# OTAVCF.net
KiCad netlist of a schematic drawn in EAGLE
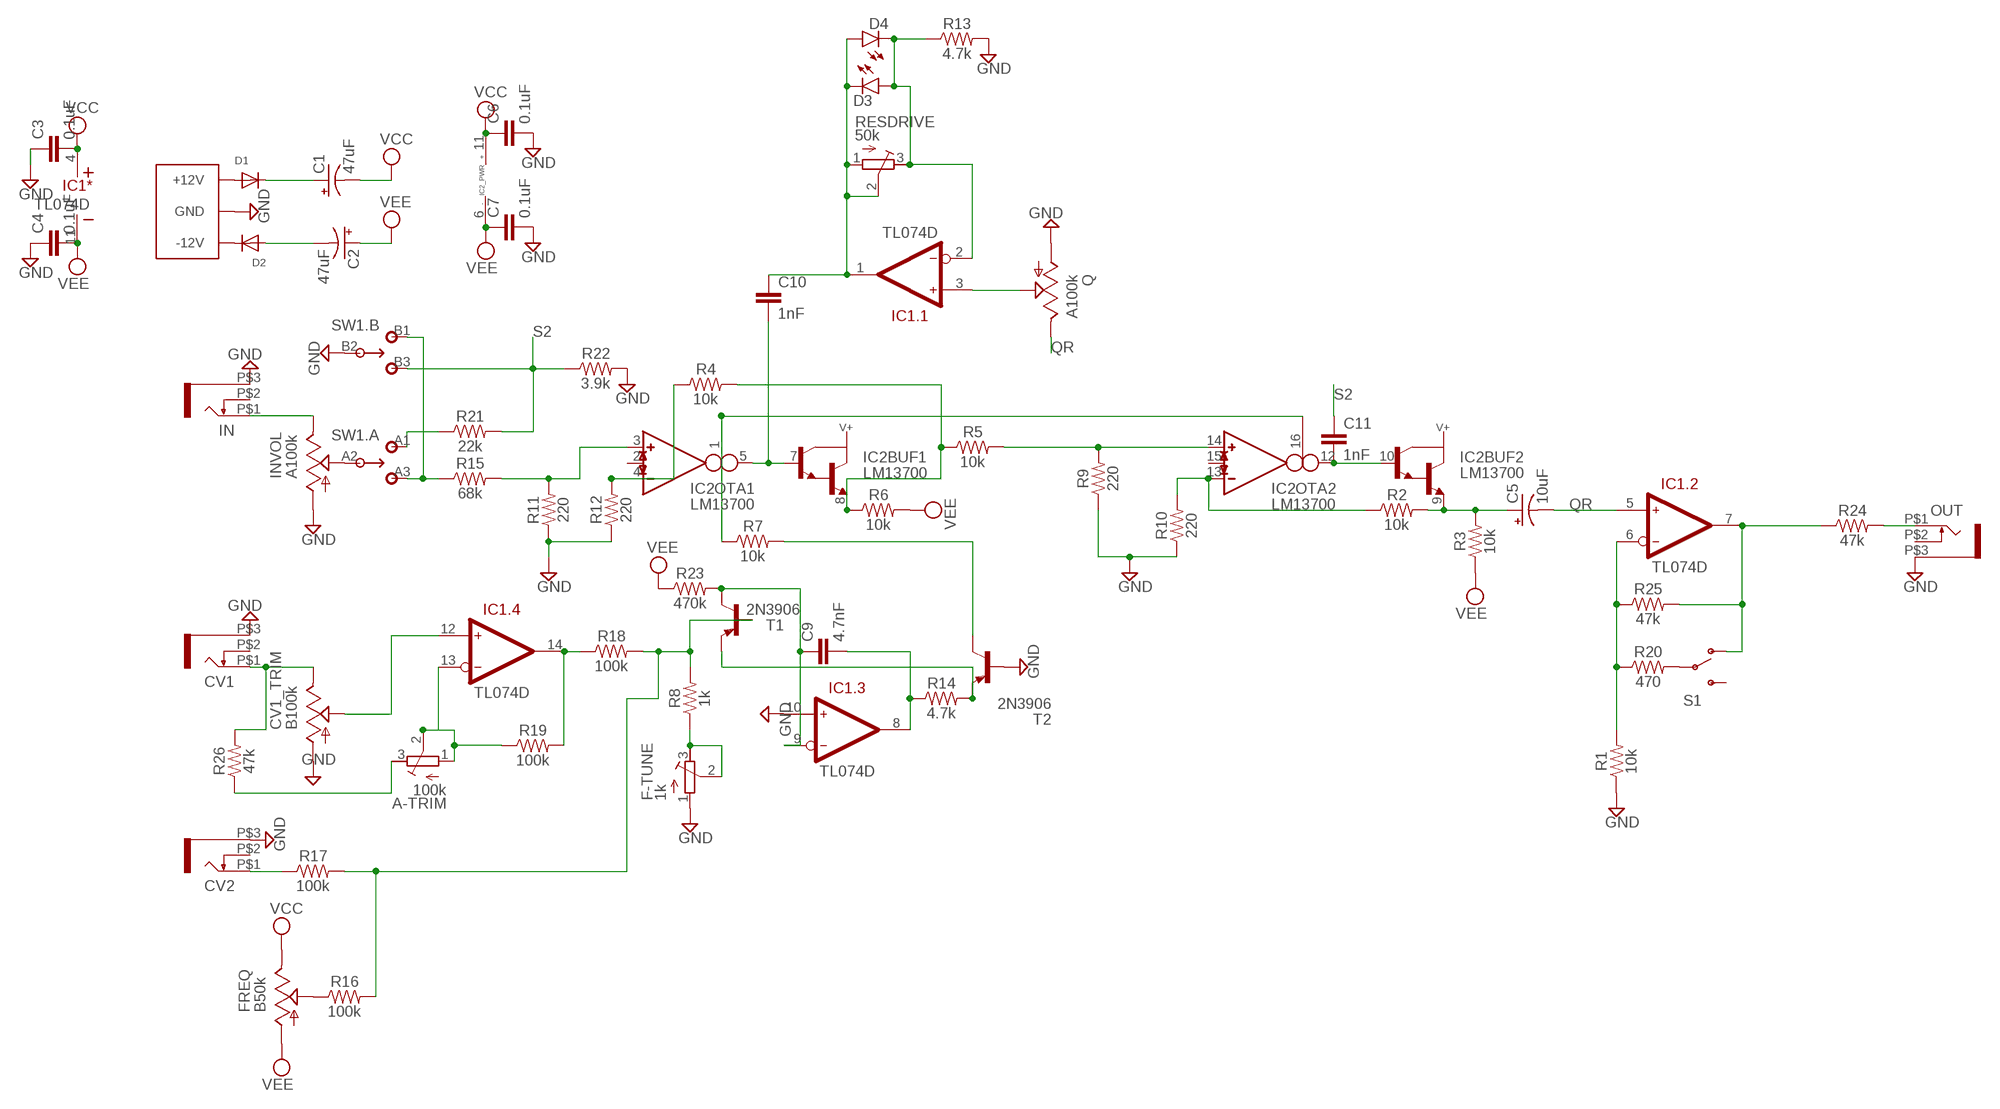
[diagram p0: schematic, sheet 1]

(export (version "E")
  (design (tool "Eeschema 10.0.6"))
  (components
    (comp (ref "A-TRIM")
      (value "100k")
      (footprint "eagle-import:RTRIM3296W")
      (libsource (lib "eagle-import") (part "R-TRIMM3296W"))
    )
    (comp (ref "C1")
      (value "47uF")
      (footprint "eagle-import:PAN_B_SMD+THRU")
      (libsource (lib "eagle-import") (part "CAP_SMD+THRUPAN_B"))
    )
    (comp (ref "C2")
      (value "47uF")
      (footprint "eagle-import:PAN_B_SMD+THRU")
      (libsource (lib "eagle-import") (part "CAP_SMD+THRUPAN_B"))
    )
    (comp (ref "C3")
      (value "0.1uF")
      (footprint "eagle-import:0603")
      (libsource (lib "eagle-import") (part "0.1UF-0603-25V-(+80/-20%)"))
    )
    (comp (ref "C4")
      (value "0.1uF")
      (footprint "eagle-import:0603")
      (libsource (lib "eagle-import") (part "0.1UF-0603-25V-(+80/-20%)"))
    )
    (comp (ref "C5")
      (value "10uF")
      (footprint "eagle-import:CPOL-RADIAL-2.5MM-5MM")
      (libsource (lib "eagle-import") (part "10UF-POLAR-RADIAL-2.5MM-25V-20%"))
    )
    (comp (ref "C6")
      (value "0.1uF")
      (footprint "eagle-import:0603")
      (libsource (lib "eagle-import") (part "0.1UF-0603-25V-(+80/-20%)"))
    )
    (comp (ref "C7")
      (value "0.1uF")
      (footprint "eagle-import:0603")
      (libsource (lib "eagle-import") (part "0.1UF-0603-25V-(+80/-20%)"))
    )
    (comp (ref "C9")
      (value "4.7nF")
      (footprint "eagle-import:0603")
      (libsource (lib "eagle-import") (part "0.1UF-0603-25V-(+80/-20%)"))
    )
    (comp (ref "C10")
      (value "1nF")
      (footprint "eagle-import:0603")
      (libsource (lib "eagle-import") (part "1.0NF/1000PF-0603-50V-10%"))
    )
    (comp (ref "C11")
      (value "1nF")
      (footprint "eagle-import:0603")
      (libsource (lib "eagle-import") (part "1.0NF/1000PF-0603-50V-10%"))
    )
    (comp (ref "CV1")
      (value "WQP-PJ301M-12_JACK")
      (footprint "eagle-import:WQP-PJ301M-12_JACK")
      (libsource (lib "eagle-import") (part "WQP-PJ301M-12_JACK"))
    )
    (comp (ref "CV1_TRIM")
      (value "B100k")
      (footprint "eagle-import:9MM_SNAP-IN_POT")
      (libsource (lib "eagle-import") (part "9MM_SNAP-IN_POT_"))
    )
    (comp (ref "CV2")
      (value "WQP-PJ301M-12_JACK")
      (footprint "eagle-import:WQP-PJ301M-12_JACK")
      (libsource (lib "eagle-import") (part "WQP-PJ301M-12_JACK"))
    )
    (comp (ref "D1")
      (value "DIODESOD-123")
      (footprint "eagle-import:SOD-123")
      (libsource (lib "eagle-import") (part "DIODESOD-123"))
    )
    (comp (ref "D2")
      (value "DIODESOD-123")
      (footprint "eagle-import:SOD-123")
      (libsource (lib "eagle-import") (part "DIODESOD-123"))
    )
    (comp (ref "D3")
      (value "LED.3")
      (footprint "eagle-import:3MM_2")
      (libsource (lib "eagle-import") (part "LED.3"))
    )
    (comp (ref "D4")
      (value "LED.3")
      (footprint "eagle-import:3MM_2")
      (libsource (lib "eagle-import") (part "LED.3"))
    )
    (comp (ref "F-TUNE")
      (value "1k")
      (footprint "eagle-import:RTRIM3296W")
      (libsource (lib "eagle-import") (part "R-TRIMM3296W"))
    )
    (comp (ref "FREQ")
      (value "B50k")
      (footprint "eagle-import:9MM_SNAP-IN_POT")
      (libsource (lib "eagle-import") (part "9MM_SNAP-IN_POT_"))
    )
    (comp (ref "IC1")
      (value "TL074D")
      (footprint "eagle-import:SO-14")
      (libsource (lib "eagle-import") (part "TL074D"))
    )
    (comp (ref "IC2")
      (value "LM13700")
      (footprint "eagle-import:SO16")
      (libsource (lib "eagle-import") (part "LM13X00_SMT"))
    )
    (comp (ref "IN")
      (value "WQP-PJ301M-12_JACK")
      (footprint "eagle-import:WQP-PJ301M-12_JACK")
      (libsource (lib "eagle-import") (part "WQP-PJ301M-12_JACK"))
    )
    (comp (ref "INVOL")
      (value "A100k")
      (footprint "eagle-import:9MM_SNAP-IN_POT")
      (libsource (lib "eagle-import") (part "9MM_SNAP-IN_POT_"))
    )
    (comp (ref "OUT")
      (value "WQP-PJ301M-12_JACK")
      (footprint "eagle-import:WQP-PJ301M-12_JACK")
      (libsource (lib "eagle-import") (part "WQP-PJ301M-12_JACK"))
    )
    (comp (ref "Q")
      (value "A100k")
      (footprint "eagle-import:9MM_SNAP-IN_POT")
      (libsource (lib "eagle-import") (part "9MM_SNAP-IN_POT_"))
    )
    (comp (ref "R1")
      (value "10k")
      (footprint "eagle-import:0603")
      (libsource (lib "eagle-import") (part "10KOHM-0603-1/10W-1%"))
    )
    (comp (ref "R2")
      (value "10k")
      (footprint "eagle-import:0603")
      (libsource (lib "eagle-import") (part "10KOHM-0603-1/10W-1%"))
    )
    (comp (ref "R3")
      (value "10k")
      (footprint "eagle-import:0603")
      (libsource (lib "eagle-import") (part "10KOHM-0603-1/10W-1%"))
    )
    (comp (ref "R4")
      (value "10k")
      (footprint "eagle-import:0603")
      (libsource (lib "eagle-import") (part "10KOHM-0603-1/10W-1%"))
    )
    (comp (ref "R5")
      (value "10k")
      (footprint "eagle-import:0603")
      (libsource (lib "eagle-import") (part "10KOHM-0603-1/10W-1%"))
    )
    (comp (ref "R6")
      (value "10k")
      (footprint "eagle-import:0603")
      (libsource (lib "eagle-import") (part "10KOHM-0603-1/10W-1%"))
    )
    (comp (ref "R7")
      (value "10k")
      (footprint "eagle-import:0603")
      (libsource (lib "eagle-import") (part "10KOHM-0603-1/10W-1%"))
    )
    (comp (ref "R8")
      (value "1k")
      (footprint "eagle-import:0603")
      (libsource (lib "eagle-import") (part "1KOHM-0603-1/10W-1%"))
    )
    (comp (ref "R9")
      (value "220")
      (footprint "eagle-import:0603")
      (libsource (lib "eagle-import") (part "220OHM-0603-1/10W-1%"))
    )
    (comp (ref "R10")
      (value "220")
      (footprint "eagle-import:0603")
      (libsource (lib "eagle-import") (part "220OHM-0603-1/10W-1%"))
    )
    (comp (ref "R11")
      (value "220")
      (footprint "eagle-import:0603")
      (libsource (lib "eagle-import") (part "220OHM-0603-1/10W-1%"))
    )
    (comp (ref "R12")
      (value "220")
      (footprint "eagle-import:0603")
      (libsource (lib "eagle-import") (part "220OHM-0603-1/10W-1%"))
    )
    (comp (ref "R13")
      (value "4.7k")
      (footprint "eagle-import:0603")
      (libsource (lib "eagle-import") (part "4.7KOHM-0603-1/10W-1%"))
    )
    (comp (ref "R14")
      (value "4.7k")
      (footprint "eagle-import:0603")
      (libsource (lib "eagle-import") (part "4.7KOHM-0603-1/10W-1%"))
    )
    (comp (ref "R15")
      (value "68k")
      (footprint "eagle-import:0603")
      (libsource (lib "eagle-import") (part "RESISTOR0603"))
    )
    (comp (ref "R16")
      (value "100k")
      (footprint "eagle-import:0603")
      (libsource (lib "eagle-import") (part "100KOHM-0603-1/10W-1%"))
    )
    (comp (ref "R17")
      (value "100k")
      (footprint "eagle-import:0603")
      (libsource (lib "eagle-import") (part "100KOHM-0603-1/10W-1%"))
    )
    (comp (ref "R18")
      (value "100k")
      (footprint "eagle-import:0603")
      (libsource (lib "eagle-import") (part "100KOHM-0603-1/10W-1%"))
    )
    (comp (ref "R19")
      (value "100k")
      (footprint "eagle-import:0603")
      (libsource (lib "eagle-import") (part "100KOHM-0603-1/10W-1%"))
    )
    (comp (ref "R20")
      (value "470")
      (footprint "eagle-import:0603")
      (libsource (lib "eagle-import") (part "470OHM-0603-1/10W-1%"))
    )
    (comp (ref "R21")
      (value "22k")
      (footprint "eagle-import:0603")
      (libsource (lib "eagle-import") (part "22KOHM-0603-1/10W-1%"))
    )
    (comp (ref "R22")
      (value "3.9k")
      (footprint "eagle-import:0603")
      (libsource (lib "eagle-import") (part "3.9KOHM-0603-1/10W-1%"))
    )
    (comp (ref "R23")
      (value "470k")
      (footprint "eagle-import:0603")
      (libsource (lib "eagle-import") (part "RESISTOR0603"))
    )
    (comp (ref "R24")
      (value "47k")
      (footprint "eagle-import:0603")
      (libsource (lib "eagle-import") (part "47KOHM-0603-1/10W-1%"))
    )
    (comp (ref "R25")
      (value "47k")
      (footprint "eagle-import:0603")
      (libsource (lib "eagle-import") (part "47KOHM-0603-1/10W-1%"))
    )
    (comp (ref "R26")
      (value "47k")
      (footprint "eagle-import:0603")
      (libsource (lib "eagle-import") (part "47KOHM-0603-1/10W-1%"))
    )
    (comp (ref "RESDRIVE")
      (value "50k")
      (footprint "eagle-import:RTRIM3296W")
      (libsource (lib "eagle-import") (part "R-TRIMM3296W"))
    )
    (comp (ref "S1")
      (value "SUBMINI_SPDT")
      (footprint "eagle-import:SUBMINI_TOGGLE")
      (libsource (lib "eagle-import") (part "SUBMINI_SPDT"))
    )
    (comp (ref "SW1")
      (value "DPDT.LUGS")
      (footprint "eagle-import:DPDT.LUGS")
      (libsource (lib "eagle-import") (part "DPDT.LUGS"))
    )
    (comp (ref "T1")
      (value "2N3906")
      (footprint "eagle-import:SOT23-BEC")
      (libsource (lib "eagle-import") (part "-PNP-SOT23-BECBC807-40"))
    )
    (comp (ref "T2")
      (value "2N3906")
      (footprint "eagle-import:SOT23-BEC")
      (libsource (lib "eagle-import") (part "-PNP-SOT23-BECBC807-40"))
    )
    (comp (ref "U$1")
      (value "EURO_POWER_LOCK")
      (footprint "eagle-import:EURO_PWR_HEADER_LOCK")
      (libsource (lib "eagle-import") (part "EURO_POWER_LOCK"))
    )
  )
  (nets
    (net (code "1") (name "/QR") (class "Default")
      (node (ref "C5") (pin "2") (pinfunction "-_2") (pintype "passive"))
      (node (ref "IC1") (pin "5") (pinfunction "IN+_5") (pintype "input"))
      (node (ref "Q") (pin "3") (pinfunction "E_3") (pintype "passive"))
    )
    (net (code "2") (name "/S2") (class "Default")
      (node (ref "C11") (pin "1") (pinfunction "1_1") (pintype "passive"))
      (node (ref "R21") (pin "2") (pinfunction "2_2") (pintype "passive"))
      (node (ref "R22") (pin "1") (pinfunction "1_1") (pintype "passive"))
      (node (ref "SW1") (pin "B3") (pinfunction "3_B3") (pintype "passive"))
    )
    (net (code "3") (name "GND") (class "Default")
      (node (ref "C3") (pin "1") (pinfunction "1_1") (pintype "passive"))
      (node (ref "C4") (pin "1") (pinfunction "1_1") (pintype "passive"))
      (node (ref "C6") (pin "2") (pinfunction "2_2") (pintype "passive"))
      (node (ref "C7") (pin "2") (pinfunction "2_2") (pintype "passive"))
      (node (ref "CV1") (pin "P$3") (pinfunction "1_P$3") (pintype "passive"))
      (node (ref "CV1_TRIM") (pin "1") (pinfunction "A_1") (pintype "passive"))
      (node (ref "CV2") (pin "P$3") (pinfunction "1_P$3") (pintype "passive"))
      (node (ref "F-TUNE") (pin "1") (pinfunction "A_1") (pintype "passive"))
      (node (ref "IC1") (pin "10") (pinfunction "IN+_10") (pintype "input"))
      (node (ref "IN") (pin "P$3") (pinfunction "1_P$3") (pintype "passive"))
      (node (ref "INVOL") (pin "1") (pinfunction "A_1") (pintype "passive"))
      (node (ref "OUT") (pin "P$3") (pinfunction "1_P$3") (pintype "passive"))
      (node (ref "Q") (pin "1") (pinfunction "A_1") (pintype "passive"))
      (node (ref "R1") (pin "1") (pinfunction "1_1") (pintype "passive"))
      (node (ref "R10") (pin "1") (pinfunction "1_1") (pintype "passive"))
      (node (ref "R11") (pin "1") (pinfunction "1_1") (pintype "passive"))
      (node (ref "R12") (pin "1") (pinfunction "1_1") (pintype "passive"))
      (node (ref "R13") (pin "2") (pinfunction "2_2") (pintype "passive"))
      (node (ref "R22") (pin "2") (pinfunction "2_2") (pintype "passive"))
      (node (ref "R9") (pin "1") (pinfunction "1_1") (pintype "passive"))
      (node (ref "SW1") (pin "B2") (pinfunction "2_B2") (pintype "passive"))
      (node (ref "T2") (pin "B") (pinfunction "B_B") (pintype "passive"))
      (node (ref "U$1") (pin "GND1") (pinfunction "GND_GND1") (pintype "bidirectional"))
      (node (ref "U$1") (pin "GND2") (pinfunction "GND_GND2") (pintype "bidirectional"))
      (node (ref "U$1") (pin "GND3") (pinfunction "GND_GND3") (pintype "bidirectional"))
      (node (ref "U$1") (pin "GND4") (pinfunction "GND_GND4") (pintype "bidirectional"))
      (node (ref "U$1") (pin "GND5") (pinfunction "GND_GND5") (pintype "bidirectional"))
      (node (ref "U$1") (pin "GND6") (pinfunction "GND_GND6") (pintype "bidirectional"))
    )
    (net (code "4") (name "Net-(A-TRIM-A)") (class "Default")
      (node (ref "A-TRIM") (pin "1") (pinfunction "A_1") (pintype "passive"))
      (node (ref "A-TRIM") (pin "2") (pinfunction "S_2") (pintype "passive"))
      (node (ref "IC1") (pin "13") (pinfunction "IN-_13") (pintype "input"))
      (node (ref "R19") (pin "1") (pinfunction "1_1") (pintype "passive"))
    )
    (net (code "5") (name "Net-(A-TRIM-E)") (class "Default")
      (node (ref "A-TRIM") (pin "3") (pinfunction "E_3") (pintype "passive"))
      (node (ref "R26") (pin "1") (pinfunction "1_1") (pintype "passive"))
    )
    (net (code "6") (name "Net-(C1-+-Pad++)") (class "Default")
      (node (ref "C1") (pin "+") (pinfunction "+_+") (pintype "passive"))
      (node (ref "C1") (pin "++") (pinfunction "+_++") (pintype "passive"))
      (node (ref "D1") (pin "C") (pinfunction "C_C") (pintype "passive"))
    )
    (net (code "7") (name "Net-(C2---Pad--)") (class "Default")
      (node (ref "C2") (pin "-") (pinfunction "-_-") (pintype "passive"))
      (node (ref "C2") (pin "--") (pinfunction "-_--") (pintype "passive"))
      (node (ref "D2") (pin "A") (pinfunction "A_A") (pintype "passive"))
    )
    (net (code "8") (name "Net-(C5-+)") (class "Default")
      (node (ref "C5") (pin "1") (pinfunction "+_1") (pintype "passive"))
      (node (ref "IC2") (pin "9") (pinfunction "E_9") (pintype "passive"))
      (node (ref "R2") (pin "2") (pinfunction "2_2") (pintype "passive"))
      (node (ref "R3") (pin "2") (pinfunction "2_2") (pintype "passive"))
    )
    (net (code "9") (name "Net-(CV1-2)") (class "Default")
      (node (ref "CV1") (pin "P$1") (pinfunction "2_P$1") (pintype "passive"))
      (node (ref "CV1_TRIM") (pin "3") (pinfunction "E_3") (pintype "passive"))
      (node (ref "R26") (pin "2") (pinfunction "2_2") (pintype "passive"))
    )
    (net (code "10") (name "Net-(CV1_TRIM-S)") (class "Default")
      (node (ref "CV1_TRIM") (pin "2") (pinfunction "S_2") (pintype "passive"))
      (node (ref "IC1") (pin "12") (pinfunction "IN+_12") (pintype "input"))
    )
    (net (code "11") (name "Net-(CV2-2)") (class "Default")
      (node (ref "CV2") (pin "P$1") (pinfunction "2_P$1") (pintype "passive"))
      (node (ref "R17") (pin "1") (pinfunction "1_1") (pintype "passive"))
    )
    (net (code "12") (name "Net-(D1-PadA)") (class "Default")
      (node (ref "D1") (pin "A") (pinfunction "A_A") (pintype "passive"))
      (node (ref "U$1") (pin "POS1") (pinfunction "+12V_POS1") (pintype "bidirectional"))
      (node (ref "U$1") (pin "POS2") (pinfunction "+12V_POS2") (pintype "bidirectional"))
    )
    (net (code "13") (name "Net-(D2-PadC)") (class "Default")
      (node (ref "D2") (pin "C") (pinfunction "C_C") (pintype "passive"))
      (node (ref "U$1") (pin "NEG1") (pinfunction "-12V_NEG1") (pintype "bidirectional"))
      (node (ref "U$1") (pin "NEG2") (pinfunction "-12V_NEG2") (pintype "bidirectional"))
    )
    (net (code "14") (name "Net-(D3-A)") (class "Default")
      (node (ref "D3") (pin "ANODE") (pinfunction "A_ANODE") (pintype "passive"))
      (node (ref "D4") (pin "P$1") (pinfunction "C_P$1") (pintype "passive"))
      (node (ref "IC1") (pin "2") (pinfunction "IN-_2") (pintype "input"))
      (node (ref "R13") (pin "1") (pinfunction "1_1") (pintype "passive"))
      (node (ref "RESDRIVE") (pin "3") (pinfunction "E_3") (pintype "passive"))
    )
    (net (code "15") (name "Net-(D3-C)") (class "Default")
      (node (ref "C10") (pin "1") (pinfunction "1_1") (pintype "passive"))
      (node (ref "D3") (pin "P$1") (pinfunction "C_P$1") (pintype "passive"))
      (node (ref "D4") (pin "ANODE") (pinfunction "A_ANODE") (pintype "passive"))
      (node (ref "IC1") (pin "1") (pinfunction "OUT_1") (pintype "output"))
      (node (ref "RESDRIVE") (pin "1") (pinfunction "A_1") (pintype "passive"))
      (node (ref "RESDRIVE") (pin "2") (pinfunction "S_2") (pintype "passive"))
    )
    (net (code "16") (name "Net-(F-TUNE-E)") (class "Default")
      (node (ref "F-TUNE") (pin "2") (pinfunction "S_2") (pintype "passive"))
      (node (ref "F-TUNE") (pin "3") (pinfunction "E_3") (pintype "passive"))
      (node (ref "R8") (pin "1") (pinfunction "1_1") (pintype "passive"))
    )
    (net (code "17") (name "Net-(FREQ-S)") (class "Default")
      (node (ref "FREQ") (pin "2") (pinfunction "S_2") (pintype "passive"))
      (node (ref "R16") (pin "1") (pinfunction "1_1") (pintype "passive"))
    )
    (net (code "18") (name "Net-(IC1B-IN+)") (class "Default")
      (node (ref "IC1") (pin "3") (pinfunction "IN+_3") (pintype "input"))
      (node (ref "Q") (pin "2") (pinfunction "S_2") (pintype "passive"))
    )
    (net (code "19") (name "Net-(IC1C-IN-)") (class "Default")
      (node (ref "IC1") (pin "6") (pinfunction "IN-_6") (pintype "input"))
      (node (ref "R1") (pin "2") (pinfunction "2_2") (pintype "passive"))
      (node (ref "R20") (pin "1") (pinfunction "1_1") (pintype "passive"))
      (node (ref "R25") (pin "1") (pinfunction "1_1") (pintype "passive"))
    )
    (net (code "20") (name "Net-(IC1C-OUT)") (class "Default")
      (node (ref "IC1") (pin "7") (pinfunction "OUT_7") (pintype "output"))
      (node (ref "R24") (pin "1") (pinfunction "1_1") (pintype "passive"))
      (node (ref "R25") (pin "2") (pinfunction "2_2") (pintype "passive"))
      (node (ref "S1") (pin "1") (pinfunction "O_1") (pintype "passive"))
    )
    (net (code "21") (name "Net-(IC1D-IN-)") (class "Default")
      (node (ref "C9") (pin "1") (pinfunction "1_1") (pintype "passive"))
      (node (ref "IC1") (pin "9") (pinfunction "IN-_9") (pintype "input"))
      (node (ref "R23") (pin "2") (pinfunction "2_2") (pintype "passive"))
      (node (ref "T1") (pin "C") (pinfunction "C_C") (pintype "passive"))
    )
    (net (code "22") (name "Net-(IC1D-OUT)") (class "Default")
      (node (ref "C9") (pin "2") (pinfunction "2_2") (pintype "passive"))
      (node (ref "IC1") (pin "8") (pinfunction "OUT_8") (pintype "output"))
      (node (ref "R14") (pin "1") (pinfunction "1_1") (pintype "passive"))
    )
    (net (code "23") (name "Net-(IC1E-OUT)") (class "Default")
      (node (ref "IC1") (pin "14") (pinfunction "OUT_14") (pintype "output"))
      (node (ref "R18") (pin "1") (pinfunction "1_1") (pintype "passive"))
      (node (ref "R19") (pin "2") (pinfunction "2_2") (pintype "passive"))
    )
    (net (code "24") (name "Net-(IC2A-B)") (class "Default")
      (node (ref "C10") (pin "2") (pinfunction "2_2") (pintype "passive"))
      (node (ref "IC2") (pin "5") (pinfunction "OUT_5") (pintype "output"))
      (node (ref "IC2") (pin "7") (pinfunction "B_7") (pintype "passive"))
    )
    (net (code "25") (name "Net-(IC2A-E)") (class "Default")
      (node (ref "IC2") (pin "8") (pinfunction "E_8") (pintype "passive"))
      (node (ref "R4") (pin "2") (pinfunction "2_2") (pintype "passive"))
      (node (ref "R5") (pin "1") (pinfunction "1_1") (pintype "passive"))
      (node (ref "R6") (pin "1") (pinfunction "1_1") (pintype "passive"))
    )
    (net (code "26") (name "Net-(IC2B-B)") (class "Default")
      (node (ref "C11") (pin "2") (pinfunction "2_2") (pintype "passive"))
      (node (ref "IC2") (pin "10") (pinfunction "B_10") (pintype "passive"))
      (node (ref "IC2") (pin "12") (pinfunction "OUT_12") (pintype "output"))
    )
    (net (code "27") (name "Net-(IC2C-IN_N)") (class "Default")
      (node (ref "IC2") (pin "4") (pinfunction "IN_N_4") (pintype "input"))
      (node (ref "R12") (pin "2") (pinfunction "2_2") (pintype "passive"))
      (node (ref "R4") (pin "1") (pinfunction "1_1") (pintype "passive"))
    )
    (net (code "28") (name "Net-(IC2C-IN_P)") (class "Default")
      (node (ref "IC2") (pin "3") (pinfunction "IN_P_3") (pintype "input"))
      (node (ref "R11") (pin "2") (pinfunction "2_2") (pintype "passive"))
      (node (ref "R15") (pin "2") (pinfunction "2_2") (pintype "passive"))
    )
    (net (code "29") (name "Net-(IC2C-I_BIAS)") (class "Default")
      (node (ref "IC2") (pin "1") (pinfunction "I_BIAS_1") (pintype "input"))
      (node (ref "IC2") (pin "16") (pinfunction "I_BIAS_16") (pintype "input"))
      (node (ref "R7") (pin "1") (pinfunction "1_1") (pintype "passive"))
    )
    (net (code "30") (name "Net-(IC2D-IN_N)") (class "Default")
      (node (ref "IC2") (pin "13") (pinfunction "IN_N_13") (pintype "input"))
      (node (ref "R10") (pin "2") (pinfunction "2_2") (pintype "passive"))
      (node (ref "R2") (pin "1") (pinfunction "1_1") (pintype "passive"))
    )
    (net (code "31") (name "Net-(IC2D-IN_P)") (class "Default")
      (node (ref "IC2") (pin "14") (pinfunction "IN_P_14") (pintype "input"))
      (node (ref "R5") (pin "2") (pinfunction "2_2") (pintype "passive"))
      (node (ref "R9") (pin "2") (pinfunction "2_2") (pintype "passive"))
    )
    (net (code "32") (name "Net-(IN-2)") (class "Default")
      (node (ref "IN") (pin "P$1") (pinfunction "2_P$1") (pintype "passive"))
      (node (ref "INVOL") (pin "3") (pinfunction "E_3") (pintype "passive"))
    )
    (net (code "33") (name "Net-(INVOL-S)") (class "Default")
      (node (ref "INVOL") (pin "2") (pinfunction "S_2") (pintype "passive"))
      (node (ref "SW1") (pin "A2") (pinfunction "2_A2") (pintype "passive"))
    )
    (net (code "34") (name "Net-(OUT-2)") (class "Default")
      (node (ref "OUT") (pin "P$1") (pinfunction "2_P$1") (pintype "passive"))
      (node (ref "R24") (pin "2") (pinfunction "2_2") (pintype "passive"))
    )
    (net (code "35") (name "Net-(R7-Pad2)") (class "Default")
      (node (ref "R7") (pin "2") (pinfunction "2_2") (pintype "passive"))
      (node (ref "T2") (pin "C") (pinfunction "C_C") (pintype "passive"))
    )
    (net (code "36") (name "Net-(R14-Pad2)") (class "Default")
      (node (ref "R14") (pin "2") (pinfunction "2_2") (pintype "passive"))
      (node (ref "T1") (pin "E") (pinfunction "E_E") (pintype "passive"))
      (node (ref "T2") (pin "E") (pinfunction "E_E") (pintype "passive"))
    )
    (net (code "37") (name "Net-(R16-Pad2)") (class "Default")
      (node (ref "R16") (pin "2") (pinfunction "2_2") (pintype "passive"))
      (node (ref "R17") (pin "2") (pinfunction "2_2") (pintype "passive"))
      (node (ref "R18") (pin "2") (pinfunction "2_2") (pintype "passive"))
      (node (ref "R8") (pin "2") (pinfunction "2_2") (pintype "passive"))
      (node (ref "T1") (pin "B") (pinfunction "B_B") (pintype "passive"))
    )
    (net (code "38") (name "Net-(S1-COMMON)") (class "Default")
      (node (ref "R20") (pin "2") (pinfunction "2_2") (pintype "passive"))
      (node (ref "S1") (pin "COM") (pinfunction "COMMON_COM") (pintype "passive"))
    )
    (net (code "39") (name "Net-(SW1A-1)") (class "Default")
      (node (ref "R21") (pin "1") (pinfunction "1_1") (pintype "passive"))
      (node (ref "SW1") (pin "A1") (pinfunction "1_A1") (pintype "passive"))
    )
    (net (code "40") (name "Net-(SW1A-3)") (class "Default")
      (node (ref "R15") (pin "1") (pinfunction "1_1") (pintype "passive"))
      (node (ref "SW1") (pin "A3") (pinfunction "3_A3") (pintype "passive"))
      (node (ref "SW1") (pin "B1") (pinfunction "1_B1") (pintype "passive"))
    )
    (net (code "41") (name "VCC") (class "Default")
      (node (ref "C1") (pin "-") (pinfunction "-_-") (pintype "passive"))
      (node (ref "C1") (pin "--") (pinfunction "-_--") (pintype "passive"))
      (node (ref "C3") (pin "2") (pinfunction "2_2") (pintype "passive"))
      (node (ref "C6") (pin "1") (pinfunction "1_1") (pintype "passive"))
      (node (ref "FREQ") (pin "3") (pinfunction "E_3") (pintype "passive"))
      (node (ref "IC1") (pin "4") (pinfunction "V+_4") (pintype "power_in"))
      (node (ref "IC2") (pin "11") (pinfunction "V+_11") (pintype "power_in"))
    )
    (net (code "42") (name "VEE") (class "Default")
      (node (ref "C2") (pin "+") (pinfunction "+_+") (pintype "passive"))
      (node (ref "C2") (pin "++") (pinfunction "+_++") (pintype "passive"))
      (node (ref "C4") (pin "2") (pinfunction "2_2") (pintype "passive"))
      (node (ref "C7") (pin "1") (pinfunction "1_1") (pintype "passive"))
      (node (ref "FREQ") (pin "1") (pinfunction "A_1") (pintype "passive"))
      (node (ref "IC1") (pin "11") (pinfunction "V-_11") (pintype "power_in"))
      (node (ref "IC2") (pin "6") (pinfunction "V-_6") (pintype "power_in"))
      (node (ref "R23") (pin "1") (pinfunction "1_1") (pintype "passive"))
      (node (ref "R3") (pin "1") (pinfunction "1_1") (pintype "passive"))
      (node (ref "R6") (pin "2") (pinfunction "2_2") (pintype "passive"))
    )
    (net (code "43") (name "unconnected-(CV1-3-PadP$2)") (class "Default")
      (node (ref "CV1") (pin "P$2") (pinfunction "3_P$2") (pintype "passive"))
    )
    (net (code "44") (name "unconnected-(CV2-3-PadP$2)") (class "Default")
      (node (ref "CV2") (pin "P$2") (pinfunction "3_P$2") (pintype "passive"))
    )
    (net (code "45") (name "unconnected-(IC2C-I_DIODE-Pad2)") (class "Default")
      (node (ref "IC2") (pin "2") (pinfunction "I_DIODE_2") (pintype "input"))
    )
    (net (code "46") (name "unconnected-(IC2D-I_DIODE-Pad15)") (class "Default")
      (node (ref "IC2") (pin "15") (pinfunction "I_DIODE_15") (pintype "input"))
    )
    (net (code "47") (name "unconnected-(IN-3-PadP$2)") (class "Default")
      (node (ref "IN") (pin "P$2") (pinfunction "3_P$2") (pintype "passive"))
    )
    (net (code "48") (name "unconnected-(OUT-3-PadP$2)") (class "Default")
      (node (ref "OUT") (pin "P$2") (pinfunction "3_P$2") (pintype "passive"))
    )
    (net (code "49") (name "unconnected-(S1-S-Pad3)") (class "Default")
      (node (ref "S1") (pin "3") (pinfunction "S_3") (pintype "passive"))
    )
  )
)
